# Schematic_proiect.net
KiCad netlist of a schematic drawn in EAGLE
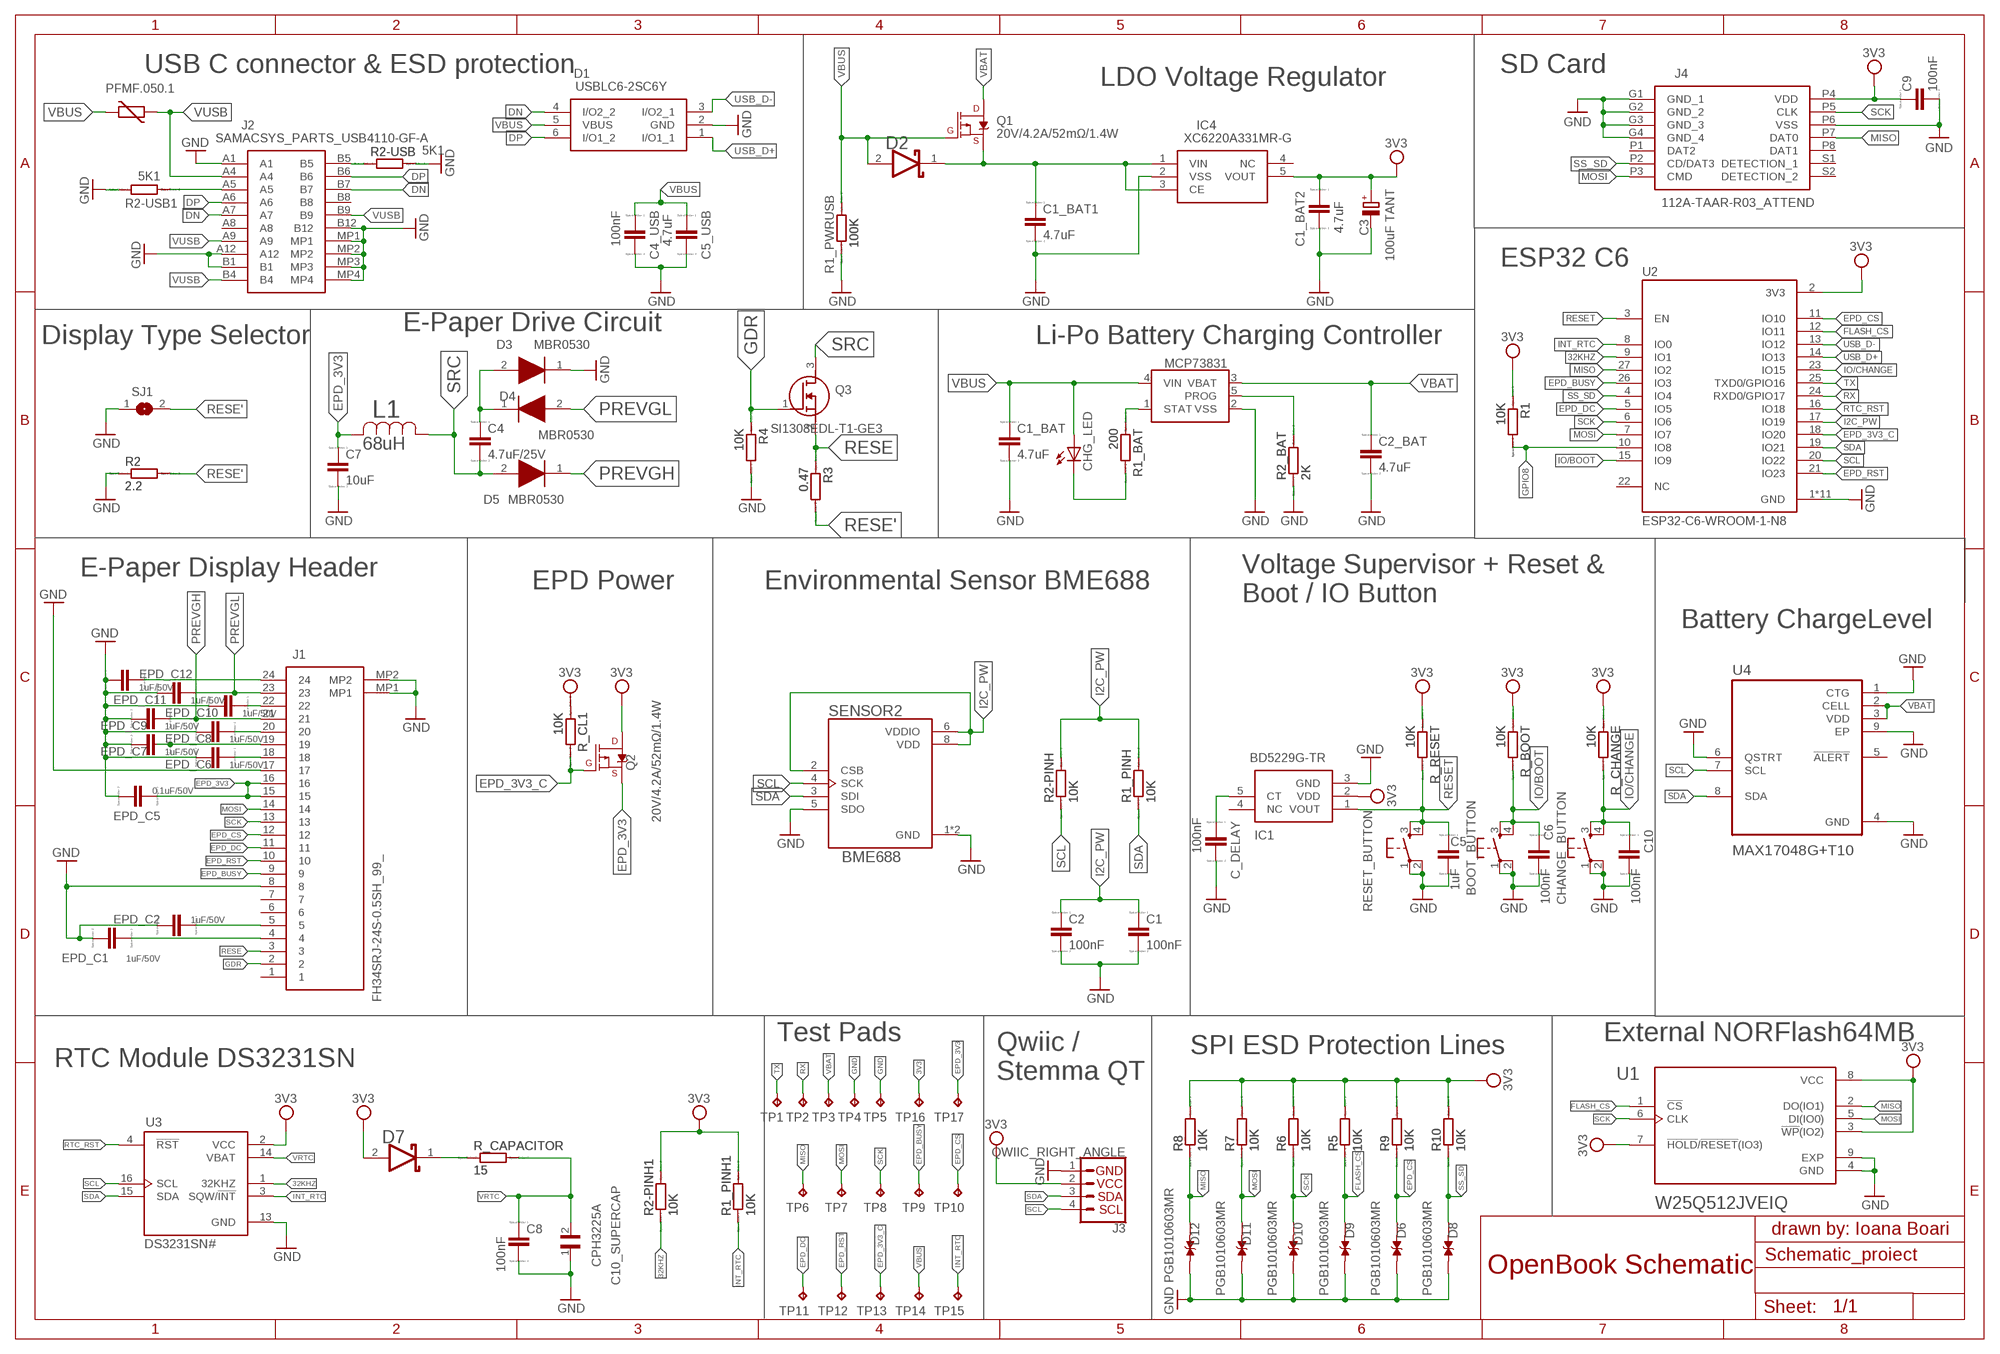
[diagram p0: schematic, sheet 1]

(export (version "E")
  (design (tool "Eeschema 10.0.6"))
  (components
    (comp (ref "BOOT_BUTTON")
      (value "BUTTON_CUSYOMV1")
      (footprint "eagle-import:MYBUTTON")
      (libsource (lib "eagle-import") (part "BUTTON_CUSYOMV1"))
    )
    (comp (ref "C1")
      (value "100nF")
      (footprint "eagle-import:ESP32_WROVER_EAGLE-LTSPICE_C0402")
      (libsource (lib "eagle-import") (part "ESP32_WROVER_EAGLE-LTSPICE_CC0402"))
    )
    (comp (ref "C1_BAT")
      (value "4.7uF")
      (footprint "eagle-import:ESP32_WROVER_EAGLE-LTSPICE_C0402")
      (libsource (lib "eagle-import") (part "ESP32_WROVER_EAGLE-LTSPICE_CC0402"))
    )
    (comp (ref "C1_BAT1")
      (value "4.7uF")
      (footprint "eagle-import:ESP32_WROVER_EAGLE-LTSPICE_C0402")
      (libsource (lib "eagle-import") (part "ESP32_WROVER_EAGLE-LTSPICE_CC0402"))
    )
    (comp (ref "C1_BAT2")
      (value "4.7uF")
      (footprint "eagle-import:EAGLE-LTSPICE_C0402")
      (libsource (lib "eagle-import") (part "EAGLE-LTSPICE_CC0402"))
    )
    (comp (ref "C2")
      (value "100nF")
      (footprint "eagle-import:ESP32_WROVER_EAGLE-LTSPICE_C0402")
      (libsource (lib "eagle-import") (part "ESP32_WROVER_EAGLE-LTSPICE_CC0402"))
    )
    (comp (ref "C2_BAT")
      (value "4.7uF")
      (footprint "eagle-import:ESP32_WROVER_EAGLE-LTSPICE_C0402")
      (libsource (lib "eagle-import") (part "ESP32_WROVER_EAGLE-LTSPICE_CC0402"))
    )
    (comp (ref "C3")
      (value "100uF TANT")
      (footprint "eagle-import:RCL_CT3528")
      (libsource (lib "eagle-import") (part "RCL_CPOL-EUCT3528"))
    )
    (comp (ref "C4")
      (value "4.7uF/25V")
      (footprint "eagle-import:ESP32_WROVER_EAGLE-LTSPICE_C0402")
      (libsource (lib "eagle-import") (part "ESP32_WROVER_EAGLE-LTSPICE_CC0402"))
    )
    (comp (ref "C4_USB")
      (value "100nF")
      (footprint "eagle-import:ESP32_WROVER_EAGLE-LTSPICE_C0402")
      (libsource (lib "eagle-import") (part "ESP32_WROVER_EAGLE-LTSPICE_CC0402"))
    )
    (comp (ref "C5")
      (value "1uF")
      (footprint "eagle-import:ESP32_WROVER_EAGLE-LTSPICE_C0402")
      (libsource (lib "eagle-import") (part "ESP32_WROVER_EAGLE-LTSPICE_CC0402"))
    )
    (comp (ref "C5_USB")
      (value "4.7uF")
      (footprint "eagle-import:ESP32_WROVER_EAGLE-LTSPICE_C0402")
      (libsource (lib "eagle-import") (part "ESP32_WROVER_EAGLE-LTSPICE_CC0402"))
    )
    (comp (ref "C6")
      (value "100nF")
      (footprint "eagle-import:ESP32_WROVER_EAGLE-LTSPICE_C0402")
      (libsource (lib "eagle-import") (part "ESP32_WROVER_EAGLE-LTSPICE_CC0402"))
    )
    (comp (ref "C7")
      (value "10uF")
      (footprint "eagle-import:ESP32_WROVER_EAGLE-LTSPICE_C0402")
      (libsource (lib "eagle-import") (part "ESP32_WROVER_EAGLE-LTSPICE_CC0402"))
    )
    (comp (ref "C8")
      (value "100nF")
      (footprint "eagle-import:ESP32_WROVER_EAGLE-LTSPICE_C0402")
      (libsource (lib "eagle-import") (part "ESP32_WROVER_EAGLE-LTSPICE_CC0402"))
    )
    (comp (ref "C9")
      (value "100nF")
      (footprint "eagle-import:ESP32_WROVER_EAGLE-LTSPICE_C0402")
      (libsource (lib "eagle-import") (part "ESP32_WROVER_EAGLE-LTSPICE_CC0402"))
    )
    (comp (ref "C10")
      (value "100nF")
      (footprint "eagle-import:ESP32_WROVER_EAGLE-LTSPICE_C0402")
      (libsource (lib "eagle-import") (part "ESP32_WROVER_EAGLE-LTSPICE_CC0402"))
    )
    (comp (ref "C10_SUPERCAP")
      (value "CPH3225A")
      (footprint "eagle-import:CAPCP3225X100N")
      (fields (field (name "MF") "Seiko Instruments"))
      (libsource (lib "eagle-import") (part "CPH3225A"))
    )
    (comp (ref "CHANGE_BUTTON")
      (value "BUTTON_CUSYOMV1")
      (footprint "eagle-import:MYBUTTON")
      (libsource (lib "eagle-import") (part "BUTTON_CUSYOMV1"))
    )
    (comp (ref "CHG_LED")
      (value "ADAFRUIT_LEDCHIP-LED0603")
      (footprint "eagle-import:ADAFRUIT_CHIP-LED0603")
      (libsource (lib "eagle-import") (part "ADAFRUIT_LEDCHIP-LED0603"))
    )
    (comp (ref "C_DELAY")
      (value "100nF")
      (footprint "eagle-import:ESP32_WROVER_EAGLE-LTSPICE_C0402")
      (libsource (lib "eagle-import") (part "ESP32_WROVER_EAGLE-LTSPICE_CC0402"))
    )
    (comp (ref "D1")
      (value "USBLC6-2SC6Y")
      (footprint "eagle-import:SOT95P280X145-6N")
      (fields (field (name "MF") "STMicroelectronics"))
      (libsource (lib "eagle-import") (part "USBLC6-2SC6Y"))
    )
    (comp (ref "D2")
      (value "ESP32_WROVER_AVX---SD0805S020S1R0_AVX_SD0805S020S1R0_0_0AVX_SD0805S020S1R0_0_0")
      (footprint "eagle-import:ESP32_WROVER_AVX---SD0805S020S1R0_AVX_SD0805S020S1R0_0")
      (fields
        (field (name "DIGIKEY_PART_NUMBER") "478-7800-1-ND")
        (field (name "MF") "AVX")
        (field (name "MOUSER_PART_NUMBER") "581-SD0805S020S1R0")
      )
      (libsource (lib "eagle-import") (part "ESP32_WROVER_AVX---SD0805S020S1R0_AVX_SD0805S020S1R0_0_0AVX_SD0805S020S1R0_0_0"))
    )
    (comp (ref "D3")
      (value "MBR0530")
      (footprint "eagle-import:SOD3716X135N")
      (fields (field (name "MF") "ON Semiconductor"))
      (libsource (lib "eagle-import") (part "MBR0530"))
    )
    (comp (ref "D4")
      (value "MBR0530")
      (footprint "eagle-import:SOD3716X135N")
      (fields (field (name "MF") "ON Semiconductor"))
      (libsource (lib "eagle-import") (part "MBR0530"))
    )
    (comp (ref "D5")
      (value "MBR0530")
      (footprint "eagle-import:SOD3716X135N")
      (fields (field (name "MF") "ON Semiconductor"))
      (libsource (lib "eagle-import") (part "MBR0530"))
    )
    (comp (ref "D6")
      (value "PGB1010603MR")
      (footprint "eagle-import:DIOC1608X36N")
      (fields (field (name "MF") "Littelfuse Inc."))
      (libsource (lib "eagle-import") (part "PGB1010603MR"))
    )
    (comp (ref "D7")
      (value "ESP32_WROVER_AVX---SD0805S020S1R0_AVX_SD0805S020S1R0_0_0AVX_SD0805S020S1R0_0_0")
      (footprint "eagle-import:ESP32_WROVER_AVX---SD0805S020S1R0_AVX_SD0805S020S1R0_0")
      (fields
        (field (name "DIGIKEY_PART_NUMBER") "478-7800-1-ND")
        (field (name "MF") "AVX")
        (field (name "MOUSER_PART_NUMBER") "581-SD0805S020S1R0")
      )
      (libsource (lib "eagle-import") (part "ESP32_WROVER_AVX---SD0805S020S1R0_AVX_SD0805S020S1R0_0_0AVX_SD0805S020S1R0_0_0"))
    )
    (comp (ref "D8")
      (value "PGB1010603MR")
      (footprint "eagle-import:DIOC1608X36N")
      (fields (field (name "MF") "Littelfuse Inc."))
      (libsource (lib "eagle-import") (part "PGB1010603MR"))
    )
    (comp (ref "D9")
      (value "PGB1010603MR")
      (footprint "eagle-import:DIOC1608X36N")
      (fields (field (name "MF") "Littelfuse Inc."))
      (libsource (lib "eagle-import") (part "PGB1010603MR"))
    )
    (comp (ref "D10")
      (value "PGB1010603MR")
      (footprint "eagle-import:DIOC1608X36N")
      (fields (field (name "MF") "Littelfuse Inc."))
      (libsource (lib "eagle-import") (part "PGB1010603MR"))
    )
    (comp (ref "D11")
      (value "PGB1010603MR")
      (footprint "eagle-import:DIOC1608X36N")
      (fields (field (name "MF") "Littelfuse Inc."))
      (libsource (lib "eagle-import") (part "PGB1010603MR"))
    )
    (comp (ref "D12")
      (value "PGB1010603MR")
      (footprint "eagle-import:DIOC1608X36N")
      (fields (field (name "MF") "Littelfuse Inc."))
      (libsource (lib "eagle-import") (part "PGB1010603MR"))
    )
    (comp (ref "EPD_C1")
      (value "1uF/50V")
      (footprint "eagle-import:ESP32_WROVER_EAGLE-LTSPICE_C0402")
      (libsource (lib "eagle-import") (part "ESP32_WROVER_EAGLE-LTSPICE_CC0402"))
    )
    (comp (ref "EPD_C2")
      (value "1uF/50V")
      (footprint "eagle-import:ESP32_WROVER_EAGLE-LTSPICE_C0402")
      (libsource (lib "eagle-import") (part "ESP32_WROVER_EAGLE-LTSPICE_CC0402"))
    )
    (comp (ref "EPD_C5")
      (value "0.1uF/50V")
      (footprint "eagle-import:ESP32_WROVER_EAGLE-LTSPICE_C0402")
      (libsource (lib "eagle-import") (part "ESP32_WROVER_EAGLE-LTSPICE_CC0402"))
    )
    (comp (ref "EPD_C6")
      (value "1uF/50V")
      (footprint "eagle-import:ESP32_WROVER_EAGLE-LTSPICE_C0402")
      (libsource (lib "eagle-import") (part "ESP32_WROVER_EAGLE-LTSPICE_CC0402"))
    )
    (comp (ref "EPD_C7")
      (value "1uF/50V")
      (footprint "eagle-import:ESP32_WROVER_EAGLE-LTSPICE_C0402")
      (libsource (lib "eagle-import") (part "ESP32_WROVER_EAGLE-LTSPICE_CC0402"))
    )
    (comp (ref "EPD_C8")
      (value "1uF/50V")
      (footprint "eagle-import:ESP32_WROVER_EAGLE-LTSPICE_C0402")
      (libsource (lib "eagle-import") (part "ESP32_WROVER_EAGLE-LTSPICE_CC0402"))
    )
    (comp (ref "EPD_C9")
      (value "1uF/50V")
      (footprint "eagle-import:ESP32_WROVER_EAGLE-LTSPICE_C0402")
      (libsource (lib "eagle-import") (part "ESP32_WROVER_EAGLE-LTSPICE_CC0402"))
    )
    (comp (ref "EPD_C10")
      (value "1uF/50V")
      (footprint "eagle-import:ESP32_WROVER_EAGLE-LTSPICE_C0402")
      (libsource (lib "eagle-import") (part "ESP32_WROVER_EAGLE-LTSPICE_CC0402"))
    )
    (comp (ref "EPD_C11")
      (value "1uF/50V")
      (footprint "eagle-import:ESP32_WROVER_EAGLE-LTSPICE_C0402")
      (libsource (lib "eagle-import") (part "ESP32_WROVER_EAGLE-LTSPICE_CC0402"))
    )
    (comp (ref "EPD_C12")
      (value "1uF/50V")
      (footprint "eagle-import:ESP32_WROVER_EAGLE-LTSPICE_C0402")
      (libsource (lib "eagle-import") (part "ESP32_WROVER_EAGLE-LTSPICE_CC0402"))
    )
    (comp (ref "IC1")
      (value "BD5229G-TR")
      (footprint "eagle-import:SOT95P280X125-5N")
      (fields (field (name "MOUSER_PART_NUMBER") "755-BD5229G-TR"))
      (libsource (lib "eagle-import") (part "BD5229G-TR"))
    )
    (comp (ref "IC4")
      (value "XC6220A331MR-G")
      (footprint "eagle-import:SOT95P280X120-5N")
      (fields (field (name "MOUSER_PART_NUMBER") "865-XC6220A331MR-G"))
      (libsource (lib "eagle-import") (part "XC6220A331MR-G"))
    )
    (comp (ref "J1")
      (value "FH34SRJ-24S-0.5SH_99_")
      (footprint "eagle-import:FH34SRJ24S05SH99")
      (fields
        (field (name "MANUFACTURER_PART_NUMBER") "FH34SRJ-24S-0.5SH(99)")
        (field (name "MOUSER_PART_NUMBER") "798-FH34SRJ24S05SH99")
      )
      (libsource (lib "eagle-import") (part "FH34SRJ-24S-0.5SH_99_"))
    )
    (comp (ref "J2")
      (value "SAMACSYS_PARTS_USB4110-GF-A")
      (footprint "eagle-import:SAMACSYS_PARTS_USB4110GFA")
      (fields
        (field (name "MANUFACTURER_PART_NUMBER") "USB4110-GF-A")
        (field (name "MOUSER_PART_NUMBER") "640-USB4110-GF-A")
      )
      (libsource (lib "eagle-import") (part "SAMACSYS_PARTS_USB4110-GF-A"))
    )
    (comp (ref "J3")
      (value "QWIIC_RIGHT_ANGLE")
      (footprint "eagle-import:JST04_1MM_RA")
      (libsource (lib "eagle-import") (part "QWIIC_CONNECTORJS-1MM"))
    )
    (comp (ref "J4")
      (value "112A-TAAR-R03_ATTEND")
      (footprint "eagle-import:112ATAARR03ATTEND")
      (fields (field (name "MANUFACTURER_PART_NUMBER") "112A-TAAR-R03 ATTEND"))
      (libsource (lib "eagle-import") (part "112A-TAAR-R03_ATTEND"))
    )
    (comp (ref "L1")
      (value "68uH")
      (footprint "eagle-import:IND_4828-WE-TPC_WRE")
      (fields
        (field (name "MANUFACTURER_PART_NUMBER") "744043680")
        (field (name "COPYRIGHT") "Copyright (C) 2024 Ultra Librarian. All rights reserved.")
      )
      (libsource (lib "eagle-import") (part "744043680IND_4828-WE-TPC_WRE"))
    )
    (comp (ref "MCP73831")
      (value "MCP73831")
      (footprint "eagle-import:ESP32_WROVER_SPARKFUN-IC-POWER_SOT23-5")
      (libsource (lib "eagle-import") (part "ESP32_WROVER_SPARKFUN-IC-POWER_MCP73831"))
    )
    (comp (ref "PFMF.050.1")
      (value "ESP32C6_VARISTORCN1812")
      (footprint "eagle-import:ESP32C6_VARISTOR_CT_CN1812")
      (libsource (lib "eagle-import") (part "ESP32C6_VARISTORCN1812"))
    )
    (comp (ref "Q1")
      (value "20V/4.2A/52mΩ/1.4W")
      (footprint "eagle-import:ESP32_WROVER_SPARKFUN-DISCRETESEMI_SOT23-3")
      (libsource (lib "eagle-import") (part "ESP32_WROVER_SPARKFUN-DISCRETESEMI_MOSFET_PCH-DMG2305UX-7"))
    )
    (comp (ref "Q2")
      (value "20V/4.2A/52mΩ/1.4W")
      (footprint "eagle-import:ESP32_WROVER_SPARKFUN-DISCRETESEMI_SOT23-3")
      (libsource (lib "eagle-import") (part "ESP32_WROVER_SPARKFUN-DISCRETESEMI_MOSFET_PCH-DMG2305UX-7"))
    )
    (comp (ref "Q3")
      (value "SI1308EDL-T1-GE3")
      (footprint "eagle-import:SOT65P210X110-3N")
      (fields (field (name "MF") "Vishay Siliconix"))
      (libsource (lib "eagle-import") (part "SI1308EDL-T1-GE3"))
    )
    (comp (ref "R1")
      (value "10K")
      (footprint "eagle-import:ESP32_WROVER_EAGLE-LTSPICE_R0402")
      (libsource (lib "eagle-import") (part "ESP32_WROVER_EAGLE-LTSPICE_RR0402"))
    )
    (comp (ref "R1_BAT")
      (value "200")
      (footprint "eagle-import:ESP32_WROVER_EAGLE-LTSPICE_R0402")
      (libsource (lib "eagle-import") (part "ESP32_WROVER_EAGLE-LTSPICE_RR0402"))
    )
    (comp (ref "R1_PINH")
      (value "10K")
      (footprint "eagle-import:ESP32_WROVER_EAGLE-LTSPICE_R0402")
      (libsource (lib "eagle-import") (part "ESP32_WROVER_EAGLE-LTSPICE_RR0402"))
    )
    (comp (ref "R1_PINH1")
      (value "10K")
      (footprint "eagle-import:ESP32_WROVER_EAGLE-LTSPICE_R0402")
      (libsource (lib "eagle-import") (part "ESP32_WROVER_EAGLE-LTSPICE_RR0402"))
    )
    (comp (ref "R1_PWRUSB")
      (value "100K")
      (footprint "eagle-import:ESP32_WROVER_EAGLE-LTSPICE_R0402")
      (libsource (lib "eagle-import") (part "ESP32_WROVER_EAGLE-LTSPICE_RR0402"))
    )
    (comp (ref "R2")
      (value "2.2")
      (footprint "eagle-import:ESP32_WROVER_EAGLE-LTSPICE_R0402")
      (libsource (lib "eagle-import") (part "ESP32_WROVER_EAGLE-LTSPICE_RR0402"))
    )
    (comp (ref "R2-PINH")
      (value "10K")
      (footprint "eagle-import:ESP32_WROVER_EAGLE-LTSPICE_R0402")
      (libsource (lib "eagle-import") (part "ESP32_WROVER_EAGLE-LTSPICE_RR0402"))
    )
    (comp (ref "R2-PINH1")
      (value "10K")
      (footprint "eagle-import:ESP32_WROVER_EAGLE-LTSPICE_R0402")
      (libsource (lib "eagle-import") (part "ESP32_WROVER_EAGLE-LTSPICE_RR0402"))
    )
    (comp (ref "R2-USB")
      (value "5K1")
      (footprint "eagle-import:ESP32_WROVER_EAGLE-LTSPICE_R0402")
      (libsource (lib "eagle-import") (part "ESP32_WROVER_EAGLE-LTSPICE_RR0402"))
    )
    (comp (ref "R2-USB1")
      (value "5K1")
      (footprint "eagle-import:ESP32_WROVER_EAGLE-LTSPICE_R0402")
      (libsource (lib "eagle-import") (part "ESP32_WROVER_EAGLE-LTSPICE_RR0402"))
    )
    (comp (ref "R2_BAT")
      (value "2K")
      (footprint "eagle-import:ESP32_WROVER_EAGLE-LTSPICE_R0402")
      (libsource (lib "eagle-import") (part "ESP32_WROVER_EAGLE-LTSPICE_RR0402"))
    )
    (comp (ref "R3")
      (value "0.47")
      (footprint "eagle-import:ESP32_WROVER_EAGLE-LTSPICE_R0402")
      (libsource (lib "eagle-import") (part "ESP32_WROVER_EAGLE-LTSPICE_RR0402"))
    )
    (comp (ref "R4")
      (value "10K")
      (footprint "eagle-import:ESP32_WROVER_EAGLE-LTSPICE_R0402")
      (libsource (lib "eagle-import") (part "ESP32_WROVER_EAGLE-LTSPICE_RR0402"))
    )
    (comp (ref "R5")
      (value "10K")
      (footprint "eagle-import:ESP32_WROVER_EAGLE-LTSPICE_R0402")
      (libsource (lib "eagle-import") (part "ESP32_WROVER_EAGLE-LTSPICE_RR0402"))
    )
    (comp (ref "R6")
      (value "10K")
      (footprint "eagle-import:ESP32_WROVER_EAGLE-LTSPICE_R0402")
      (libsource (lib "eagle-import") (part "ESP32_WROVER_EAGLE-LTSPICE_RR0402"))
    )
    (comp (ref "R7")
      (value "10K")
      (footprint "eagle-import:ESP32_WROVER_EAGLE-LTSPICE_R0402")
      (libsource (lib "eagle-import") (part "ESP32_WROVER_EAGLE-LTSPICE_RR0402"))
    )
    (comp (ref "R8")
      (value "10K")
      (footprint "eagle-import:ESP32_WROVER_EAGLE-LTSPICE_R0402")
      (libsource (lib "eagle-import") (part "ESP32_WROVER_EAGLE-LTSPICE_RR0402"))
    )
    (comp (ref "R9")
      (value "10K")
      (footprint "eagle-import:ESP32_WROVER_EAGLE-LTSPICE_R0402")
      (libsource (lib "eagle-import") (part "ESP32_WROVER_EAGLE-LTSPICE_RR0402"))
    )
    (comp (ref "R10")
      (value "10K")
      (footprint "eagle-import:ESP32_WROVER_EAGLE-LTSPICE_R0402")
      (libsource (lib "eagle-import") (part "ESP32_WROVER_EAGLE-LTSPICE_RR0402"))
    )
    (comp (ref "RESET_BUTTON")
      (value "BUTTON_CUSYOMV1")
      (footprint "eagle-import:MYBUTTON")
      (libsource (lib "eagle-import") (part "BUTTON_CUSYOMV1"))
    )
    (comp (ref "R_BOOT")
      (value "10K")
      (footprint "eagle-import:ESP32_WROVER_EAGLE-LTSPICE_R0402")
      (libsource (lib "eagle-import") (part "ESP32_WROVER_EAGLE-LTSPICE_RR0402"))
    )
    (comp (ref "R_CAPACITOR")
      (value "15")
      (footprint "eagle-import:ESP32_WROVER_EAGLE-LTSPICE_R0402")
      (libsource (lib "eagle-import") (part "ESP32_WROVER_EAGLE-LTSPICE_RR0402"))
    )
    (comp (ref "R_CHANGE")
      (value "10K")
      (footprint "eagle-import:ESP32_WROVER_EAGLE-LTSPICE_R0402")
      (libsource (lib "eagle-import") (part "ESP32_WROVER_EAGLE-LTSPICE_RR0402"))
    )
    (comp (ref "R_CL1")
      (value "10K")
      (footprint "eagle-import:ESP32_WROVER_EAGLE-LTSPICE_R0402")
      (libsource (lib "eagle-import") (part "ESP32_WROVER_EAGLE-LTSPICE_RR0402"))
    )
    (comp (ref "R_RESET")
      (value "10K")
      (footprint "eagle-import:ESP32_WROVER_EAGLE-LTSPICE_R0402")
      (libsource (lib "eagle-import") (part "ESP32_WROVER_EAGLE-LTSPICE_RR0402"))
    )
    (comp (ref "SENSOR2")
      (value "BME688")
      (footprint "eagle-import:ESP32_WROVER_BME680_PSON80P300X300X100-8N")
      (fields (field (name "MF") "Bosch Sensortec") (field (name "MP") "BME680"))
      (libsource (lib "eagle-import") (part "ESP32_WROVER_BME680_BME680"))
    )
    (comp (ref "SJ1") (value "SJ") (footprint "eagle-import:SJ") (libsource (lib "eagle-import") (part "SJ")))
    (comp (ref "TP1")
      (value "TPTP20R")
      (footprint "eagle-import:TP20R")
      (libsource (lib "eagle-import") (part "TPTP20R"))
    )
    (comp (ref "TP2")
      (value "TPTP20R")
      (footprint "eagle-import:TP20R")
      (libsource (lib "eagle-import") (part "TPTP20R"))
    )
    (comp (ref "TP3")
      (value "TPTP20R")
      (footprint "eagle-import:TP20R")
      (libsource (lib "eagle-import") (part "TPTP20R"))
    )
    (comp (ref "TP4")
      (value "TPTP20R")
      (footprint "eagle-import:TP20R")
      (libsource (lib "eagle-import") (part "TPTP20R"))
    )
    (comp (ref "TP5")
      (value "TPTP20R")
      (footprint "eagle-import:TP20R")
      (libsource (lib "eagle-import") (part "TPTP20R"))
    )
    (comp (ref "TP6")
      (value "TPTP20R")
      (footprint "eagle-import:TP20R")
      (libsource (lib "eagle-import") (part "TPTP20R"))
    )
    (comp (ref "TP7")
      (value "TPTP20R")
      (footprint "eagle-import:TP20R")
      (libsource (lib "eagle-import") (part "TPTP20R"))
    )
    (comp (ref "TP8")
      (value "TPTP20R")
      (footprint "eagle-import:TP20R")
      (libsource (lib "eagle-import") (part "TPTP20R"))
    )
    (comp (ref "TP9")
      (value "TPTP20R")
      (footprint "eagle-import:TP20R")
      (libsource (lib "eagle-import") (part "TPTP20R"))
    )
    (comp (ref "TP10")
      (value "TPTP20R")
      (footprint "eagle-import:TP20R")
      (libsource (lib "eagle-import") (part "TPTP20R"))
    )
    (comp (ref "TP11")
      (value "TPTP20R")
      (footprint "eagle-import:TP20R")
      (libsource (lib "eagle-import") (part "TPTP20R"))
    )
    (comp (ref "TP12")
      (value "TPTP20R")
      (footprint "eagle-import:TP20R")
      (libsource (lib "eagle-import") (part "TPTP20R"))
    )
    (comp (ref "TP13")
      (value "TPTP20R")
      (footprint "eagle-import:TP20R")
      (libsource (lib "eagle-import") (part "TPTP20R"))
    )
    (comp (ref "TP14")
      (value "TPTP20R")
      (footprint "eagle-import:TP20R")
      (libsource (lib "eagle-import") (part "TPTP20R"))
    )
    (comp (ref "TP15")
      (value "TPTP20R")
      (footprint "eagle-import:TP20R")
      (libsource (lib "eagle-import") (part "TPTP20R"))
    )
    (comp (ref "TP16")
      (value "TPTP20R")
      (footprint "eagle-import:TP20R")
      (libsource (lib "eagle-import") (part "TPTP20R"))
    )
    (comp (ref "TP17")
      (value "TPTP20R")
      (footprint "eagle-import:TP20R")
      (libsource (lib "eagle-import") (part "TPTP20R"))
    )
    (comp (ref "U1")
      (value "W25Q512JVEIQ")
      (footprint "eagle-import:SON127P600X800X80-9N")
      (fields (field (name "MF") "Winbond Electronics"))
      (libsource (lib "eagle-import") (part "W25Q512JVEIQ"))
    )
    (comp (ref "U2")
      (value "ESP32-C6-WROOM-1-N8")
      (footprint "eagle-import:XCVR_ESP32-C6-WROOM-1-N8")
      (fields (field (name "MF") "Espressif Systems"))
      (libsource (lib "eagle-import") (part "ESP32-C6-WROOM-1-N8"))
    )
    (comp (ref "U3")
      (value "DS3231SN#")
      (footprint "eagle-import:SOIC127P1032X265-16N")
      (fields (field (name "MF") "Analog Devices"))
      (libsource (lib "eagle-import") (part "DS3231SN#"))
    )
    (comp (ref "U4")
      (value "MAX17048G+T10")
      (footprint "eagle-import:SON50P200X200X80-9N")
      (fields (field (name "MF") "Analog Devices"))
      (libsource (lib "eagle-import") (part "MAX17048G+T10"))
    )
  )
  (nets
    (net (code "1") (name "3V3") (class "Default")
      (node (ref "C1_BAT2") (pin "1") (pinfunction "1_1") (pintype "passive"))
      (node (ref "C3") (pin "+") (pinfunction "+_+") (pintype "passive"))
      (node (ref "C9") (pin "1") (pinfunction "1_1") (pintype "passive"))
      (node (ref "D7") (pin "2") (pinfunction "ANODE_2") (pintype "bidirectional"))
      (node (ref "IC1") (pin "2") (pinfunction "VDD_2") (pintype "bidirectional"))
      (node (ref "IC4") (pin "5") (pinfunction "VOUT_5") (pintype "bidirectional"))
      (node (ref "J3") (pin "2") (pinfunction "2_2") (pintype "power_in"))
      (node (ref "J4") (pin "P4") (pinfunction "VDD_P4") (pintype "bidirectional"))
      (node (ref "Q2") (pin "3") (pinfunction "D_3") (pintype "bidirectional"))
      (node (ref "R1") (pin "1") (pinfunction "1_1") (pintype "passive"))
      (node (ref "R10") (pin "2") (pinfunction "2_2") (pintype "passive"))
      (node (ref "R1_PINH1") (pin "2") (pinfunction "2_2") (pintype "passive"))
      (node (ref "R2-PINH1") (pin "2") (pinfunction "2_2") (pintype "passive"))
      (node (ref "R5") (pin "2") (pinfunction "2_2") (pintype "passive"))
      (node (ref "R6") (pin "2") (pinfunction "2_2") (pintype "passive"))
      (node (ref "R7") (pin "2") (pinfunction "2_2") (pintype "passive"))
      (node (ref "R8") (pin "2") (pinfunction "2_2") (pintype "passive"))
      (node (ref "R9") (pin "2") (pinfunction "2_2") (pintype "passive"))
      (node (ref "R_BOOT") (pin "1") (pinfunction "1_1") (pintype "passive"))
      (node (ref "R_CHANGE") (pin "1") (pinfunction "1_1") (pintype "passive"))
      (node (ref "R_CL1") (pin "1") (pinfunction "1_1") (pintype "passive"))
      (node (ref "R_RESET") (pin "1") (pinfunction "1_1") (pintype "passive"))
      (node (ref "TP16") (pin "TP") (pinfunction "TP_TP") (pintype "input"))
      (node (ref "U1") (pin "3") (pinfunction "~{WP}(IO2)_3") (pintype "bidirectional"))
      (node (ref "U1") (pin "7") (pinfunction "~{HOLD}/~{RESET}(IO3)_7") (pintype "bidirectional"))
      (node (ref "U1") (pin "8") (pinfunction "VCC_8") (pintype "power_in"))
      (node (ref "U2") (pin "2") (pinfunction "3V3_2") (pintype "power_in"))
      (node (ref "U3") (pin "2") (pinfunction "VCC_2") (pintype "power_in"))
    )
    (net (code "2") (name "32KHZ") (class "Default")
      (node (ref "R2-PINH1") (pin "1") (pinfunction "1_1") (pintype "passive"))
      (node (ref "U2") (pin "9") (pinfunction "IO1_9") (pintype "bidirectional"))
      (node (ref "U3") (pin "1") (pinfunction "32KHZ_1") (pintype "output"))
    )
    (net (code "3") (name "DN") (class "Default")
      (node (ref "D1") (pin "4") (pinfunction "I/O2_2_4") (pintype "bidirectional"))
      (node (ref "J2") (pin "A7") (pinfunction "A7_A7") (pintype "bidirectional"))
      (node (ref "J2") (pin "B7") (pinfunction "B7_B7") (pintype "bidirectional"))
    )
    (net (code "4") (name "DP") (class "Default")
      (node (ref "D1") (pin "6") (pinfunction "I/O1_2_6") (pintype "bidirectional"))
      (node (ref "J2") (pin "A6") (pinfunction "A6_A6") (pintype "bidirectional"))
      (node (ref "J2") (pin "B6") (pinfunction "B6_B6") (pintype "bidirectional"))
    )
    (net (code "5") (name "EPD_3V3") (class "Default")
      (node (ref "C7") (pin "1") (pinfunction "1_1") (pintype "passive"))
      (node (ref "EPD_C5") (pin "1") (pinfunction "1_1") (pintype "passive"))
      (node (ref "J1") (pin "15") (pinfunction "15_15") (pintype "bidirectional"))
      (node (ref "J1") (pin "16") (pinfunction "16_16") (pintype "bidirectional"))
      (node (ref "L1") (pin "2") (pinfunction "2_2") (pintype "passive"))
      (node (ref "Q2") (pin "2") (pinfunction "S_2") (pintype "bidirectional"))
      (node (ref "TP17") (pin "TP") (pinfunction "TP_TP") (pintype "input"))
    )
    (net (code "6") (name "EPD_3V3_C") (class "Default")
      (node (ref "Q2") (pin "1") (pinfunction "G_1") (pintype "bidirectional"))
      (node (ref "R_CL1") (pin "2") (pinfunction "2_2") (pintype "passive"))
      (node (ref "TP13") (pin "TP") (pinfunction "TP_TP") (pintype "input"))
      (node (ref "U2") (pin "18") (pinfunction "IO20_18") (pintype "bidirectional"))
    )
    (net (code "7") (name "EPD_BUSY") (class "Default")
      (node (ref "J1") (pin "9") (pinfunction "9_9") (pintype "bidirectional"))
      (node (ref "TP9") (pin "TP") (pinfunction "TP_TP") (pintype "input"))
      (node (ref "U2") (pin "26") (pinfunction "IO3_26") (pintype "bidirectional"))
    )
    (net (code "8") (name "EPD_CS") (class "Default")
      (node (ref "D6") (pin "1") (pinfunction "1_1") (pintype "passive"))
      (node (ref "J1") (pin "12") (pinfunction "12_12") (pintype "bidirectional"))
      (node (ref "R9") (pin "1") (pinfunction "1_1") (pintype "passive"))
      (node (ref "TP10") (pin "TP") (pinfunction "TP_TP") (pintype "input"))
      (node (ref "U2") (pin "11") (pinfunction "IO10_11") (pintype "bidirectional"))
    )
    (net (code "9") (name "EPD_DC") (class "Default")
      (node (ref "J1") (pin "11") (pinfunction "11_11") (pintype "bidirectional"))
      (node (ref "TP11") (pin "TP") (pinfunction "TP_TP") (pintype "input"))
      (node (ref "U2") (pin "5") (pinfunction "IO5_5") (pintype "bidirectional"))
    )
    (net (code "10") (name "EPD_RST") (class "Default")
      (node (ref "J1") (pin "10") (pinfunction "10_10") (pintype "bidirectional"))
      (node (ref "TP12") (pin "TP") (pinfunction "TP_TP") (pintype "input"))
      (node (ref "U2") (pin "21") (pinfunction "IO23_21") (pintype "bidirectional"))
    )
    (net (code "11") (name "FLASH_CS") (class "Default")
      (node (ref "D9") (pin "1") (pinfunction "1_1") (pintype "passive"))
      (node (ref "R5") (pin "1") (pinfunction "1_1") (pintype "passive"))
      (node (ref "U1") (pin "1") (pinfunction "~{CS}_1") (pintype "input"))
      (node (ref "U2") (pin "12") (pinfunction "IO11_12") (pintype "bidirectional"))
    )
    (net (code "12") (name "GDR") (class "Default")
      (node (ref "J1") (pin "2") (pinfunction "2_2") (pintype "bidirectional"))
      (node (ref "Q3") (pin "1") (pinfunction "G_1") (pintype "bidirectional"))
      (node (ref "R4") (pin "1") (pinfunction "1_1") (pintype "passive"))
    )
    (net (code "13") (name "GND") (class "Default")
      (node (ref "BOOT_BUTTON") (pin "1") (pinfunction "1_1") (pintype "passive"))
      (node (ref "BOOT_BUTTON") (pin "2") (pinfunction "2_2") (pintype "passive"))
      (node (ref "C1") (pin "2") (pinfunction "2_2") (pintype "passive"))
      (node (ref "C10") (pin "2") (pinfunction "2_2") (pintype "passive"))
      (node (ref "C10_SUPERCAP") (pin "1") (pinfunction "1_1") (pintype "passive"))
      (node (ref "C1_BAT") (pin "2") (pinfunction "2_2") (pintype "passive"))
      (node (ref "C1_BAT1") (pin "2") (pinfunction "2_2") (pintype "passive"))
      (node (ref "C1_BAT2") (pin "2") (pinfunction "2_2") (pintype "passive"))
      (node (ref "C2") (pin "2") (pinfunction "2_2") (pintype "passive"))
      (node (ref "C2_BAT") (pin "2") (pinfunction "2_2") (pintype "passive"))
      (node (ref "C3") (pin "-") (pinfunction "-_-") (pintype "passive"))
      (node (ref "C4_USB") (pin "2") (pinfunction "2_2") (pintype "passive"))
      (node (ref "C5") (pin "2") (pinfunction "2_2") (pintype "passive"))
      (node (ref "C5_USB") (pin "2") (pinfunction "2_2") (pintype "passive"))
      (node (ref "C6") (pin "2") (pinfunction "2_2") (pintype "passive"))
      (node (ref "C7") (pin "2") (pinfunction "2_2") (pintype "passive"))
      (node (ref "C8") (pin "2") (pinfunction "2_2") (pintype "passive"))
      (node (ref "C9") (pin "2") (pinfunction "2_2") (pintype "passive"))
      (node (ref "CHANGE_BUTTON") (pin "1") (pinfunction "1_1") (pintype "passive"))
      (node (ref "CHANGE_BUTTON") (pin "2") (pinfunction "2_2") (pintype "passive"))
      (node (ref "C_DELAY") (pin "2") (pinfunction "2_2") (pintype "passive"))
      (node (ref "D1") (pin "2") (pinfunction "GND_2") (pintype "bidirectional"))
      (node (ref "D10") (pin "2") (pinfunction "2_2") (pintype "passive"))
      (node (ref "D11") (pin "2") (pinfunction "2_2") (pintype "passive"))
      (node (ref "D12") (pin "2") (pinfunction "2_2") (pintype "passive"))
      (node (ref "D3") (pin "1") (pinfunction "K_1") (pintype "bidirectional"))
      (node (ref "D6") (pin "2") (pinfunction "2_2") (pintype "passive"))
      (node (ref "D8") (pin "2") (pinfunction "2_2") (pintype "passive"))
      (node (ref "D9") (pin "2") (pinfunction "2_2") (pintype "passive"))
      (node (ref "EPD_C1") (pin "2") (pinfunction "2_2") (pintype "passive"))
      (node (ref "EPD_C10") (pin "2") (pinfunction "2_2") (pintype "passive"))
      (node (ref "EPD_C11") (pin "2") (pinfunction "2_2") (pintype "passive"))
      (node (ref "EPD_C12") (pin "2") (pinfunction "2_2") (pintype "passive"))
      (node (ref "EPD_C2") (pin "2") (pinfunction "2_2") (pintype "passive"))
      (node (ref "EPD_C5") (pin "2") (pinfunction "2_2") (pintype "passive"))
      (node (ref "EPD_C6") (pin "2") (pinfunction "2_2") (pintype "passive"))
      (node (ref "EPD_C7") (pin "2") (pinfunction "2_2") (pintype "passive"))
      (node (ref "EPD_C8") (pin "2") (pinfunction "2_2") (pintype "passive"))
      (node (ref "EPD_C9") (pin "2") (pinfunction "2_2") (pintype "passive"))
      (node (ref "IC1") (pin "3") (pinfunction "GND_3") (pintype "bidirectional"))
      (node (ref "IC4") (pin "2") (pinfunction "VSS_2") (pintype "bidirectional"))
      (node (ref "J1") (pin "17") (pinfunction "17_17") (pintype "bidirectional"))
      (node (ref "J1") (pin "8") (pinfunction "8_8") (pintype "bidirectional"))
      (node (ref "J1") (pin "MP1") (pinfunction "MP1_MP1") (pintype "bidirectional"))
      (node (ref "J1") (pin "MP2") (pinfunction "MP2_MP2") (pintype "bidirectional"))
      (node (ref "J2") (pin "A1") (pinfunction "A1_A1") (pintype "bidirectional"))
      (node (ref "J2") (pin "A12") (pinfunction "A12_A12") (pintype "bidirectional"))
      (node (ref "J2") (pin "B1") (pinfunction "B1_B1") (pintype "bidirectional"))
      (node (ref "J2") (pin "B12") (pinfunction "B12_B12") (pintype "bidirectional"))
      (node (ref "J2") (pin "MP1") (pinfunction "MP1_MP1") (pintype "bidirectional"))
      (node (ref "J2") (pin "MP2") (pinfunction "MP2_MP2") (pintype "bidirectional"))
      (node (ref "J2") (pin "MP3") (pinfunction "MP3_MP3") (pintype "bidirectional"))
      (node (ref "J2") (pin "MP4") (pinfunction "MP4_MP4") (pintype "bidirectional"))
      (node (ref "J3") (pin "1") (pinfunction "1_1") (pintype "power_in"))
      (node (ref "J4") (pin "G1") (pinfunction "GND_1_G1") (pintype "bidirectional"))
      (node (ref "J4") (pin "G2") (pinfunction "GND_2_G2") (pintype "bidirectional"))
      (node (ref "J4") (pin "G3") (pinfunction "GND_3_G3") (pintype "bidirectional"))
      (node (ref "J4") (pin "G4") (pinfunction "GND_4_G4") (pintype "bidirectional"))
      (node (ref "J4") (pin "P6") (pinfunction "VSS_P6") (pintype "bidirectional"))
      (node (ref "MCP73831") (pin "2") (pinfunction "VSS_2") (pintype "power_in"))
      (node (ref "R1_PWRUSB") (pin "1") (pinfunction "1_1") (pintype "passive"))
      (node (ref "R2") (pin "1") (pinfunction "1_1") (pintype "passive"))
      (node (ref "R2-USB") (pin "2") (pinfunction "2_2") (pintype "passive"))
      (node (ref "R2-USB1") (pin "1") (pinfunction "1_1") (pintype "passive"))
      (node (ref "R2_BAT") (pin "1") (pinfunction "1_1") (pintype "passive"))
      (node (ref "R4") (pin "2") (pinfunction "2_2") (pintype "passive"))
      (node (ref "RESET_BUTTON") (pin "1") (pinfunction "1_1") (pintype "passive"))
      (node (ref "RESET_BUTTON") (pin "2") (pinfunction "2_2") (pintype "passive"))
      (node (ref "SENSOR2") (pin "1") (pinfunction "GND_1") (pintype "power_in"))
      (node (ref "SENSOR2") (pin "5") (pinfunction "SDO_5") (pintype "bidirectional"))
      (node (ref "SENSOR2") (pin "7") (pinfunction "GND_7") (pintype "power_in"))
      (node (ref "SJ1") (pin "1") (pinfunction "1_1") (pintype "passive"))
      (node (ref "TP4") (pin "TP") (pinfunction "TP_TP") (pintype "input"))
      (node (ref "TP5") (pin "TP") (pinfunction "TP_TP") (pintype "input"))
      (node (ref "U1") (pin "4") (pinfunction "GND_4") (pintype "power_in"))
      (node (ref "U1") (pin "9") (pinfunction "EXP_9") (pintype "passive"))
      (node (ref "U2") (pin "1") (pinfunction "GND_1") (pintype "power_in"))
      (node (ref "U2") (pin "28") (pinfunction "GND_28") (pintype "power_in"))
      (node (ref "U2") (pin "29_1") (pinfunction "GND_29_1") (pintype "power_in"))
      (node (ref "U2") (pin "29_2") (pinfunction "GND_29_2") (pintype "power_in"))
      (node (ref "U2") (pin "29_3") (pinfunction "GND_29_3") (pintype "power_in"))
      (node (ref "U2") (pin "29_4") (pinfunction "GND_29_4") (pintype "power_in"))
      (node (ref "U2") (pin "29_5") (pinfunction "GND_29_5") (pintype "power_in"))
      (node (ref "U2") (pin "29_6") (pinfunction "GND_29_6") (pintype "power_in"))
      (node (ref "U2") (pin "29_7") (pinfunction "GND_29_7") (pintype "power_in"))
      (node (ref "U2") (pin "29_8") (pinfunction "GND_29_8") (pintype "power_in"))
      (node (ref "U2") (pin "29_9") (pinfunction "GND_29_9") (pintype "power_in"))
      (node (ref "U3") (pin "13") (pinfunction "GND_13") (pintype "power_in"))
      (node (ref "U4") (pin "1") (pinfunction "CTG_1") (pintype "power_in"))
      (node (ref "U4") (pin "4") (pinfunction "GND_4") (pintype "power_in"))
      (node (ref "U4") (pin "6") (pinfunction "QSTRT_6") (pintype "input"))
      (node (ref "U4") (pin "9") (pinfunction "EP_9") (pintype "power_in"))
    )
    (net (code "14") (name "GPIO8") (class "Default")
      (node (ref "R1") (pin "2") (pinfunction "2_2") (pintype "passive"))
      (node (ref "U2") (pin "10") (pinfunction "IO8_10") (pintype "bidirectional"))
    )
    (net (code "15") (name "I2C_PW") (class "Default")
      (node (ref "C1") (pin "1") (pinfunction "1_1") (pintype "passive"))
      (node (ref "C2") (pin "1") (pinfunction "1_1") (pintype "passive"))
      (node (ref "R1_PINH") (pin "2") (pinfunction "2_2") (pintype "passive"))
      (node (ref "R2-PINH") (pin "2") (pinfunction "2_2") (pintype "passive"))
      (node (ref "SENSOR2") (pin "2") (pinfunction "CSB_2") (pintype "input"))
      (node (ref "SENSOR2") (pin "6") (pinfunction "VDDIO_6") (pintype "power_in"))
      (node (ref "SENSOR2") (pin "8") (pinfunction "VDD_8") (pintype "power_in"))
      (node (ref "U2") (pin "17") (pinfunction "IO19_17") (pintype "bidirectional"))
    )
    (net (code "16") (name "INT_RTC") (class "Default")
      (node (ref "R1_PINH1") (pin "1") (pinfunction "1_1") (pintype "passive"))
      (node (ref "TP15") (pin "TP") (pinfunction "TP_TP") (pintype "input"))
      (node (ref "U2") (pin "8") (pinfunction "IO0_8") (pintype "bidirectional"))
      (node (ref "U3") (pin "3") (pinfunction "SQW/~{INT}_3") (pintype "output"))
    )
    (net (code "17") (name "IO{slash}BOOT") (class "Default")
      (node (ref "BOOT_BUTTON") (pin "3") (pinfunction "3_3") (pintype "passive"))
      (node (ref "BOOT_BUTTON") (pin "4") (pinfunction "4_4") (pintype "passive"))
      (node (ref "C6") (pin "1") (pinfunction "1_1") (pintype "passive"))
      (node (ref "R_BOOT") (pin "2") (pinfunction "2_2") (pintype "passive"))
      (node (ref "U2") (pin "15") (pinfunction "IO9_15") (pintype "bidirectional"))
    )
    (net (code "18") (name "IO{slash}CHANGE") (class "Default")
      (node (ref "C10") (pin "1") (pinfunction "1_1") (pintype "passive"))
      (node (ref "CHANGE_BUTTON") (pin "3") (pinfunction "3_3") (pintype "passive"))
      (node (ref "CHANGE_BUTTON") (pin "4") (pinfunction "4_4") (pintype "passive"))
      (node (ref "R_CHANGE") (pin "2") (pinfunction "2_2") (pintype "passive"))
      (node (ref "U2") (pin "23") (pinfunction "IO15_23") (pintype "bidirectional"))
    )
    (net (code "19") (name "MISO") (class "Default")
      (node (ref "D12") (pin "1") (pinfunction "1_1") (pintype "passive"))
      (node (ref "J4") (pin "P7") (pinfunction "DAT0_P7") (pintype "bidirectional"))
      (node (ref "R8") (pin "1") (pinfunction "1_1") (pintype "passive"))
      (node (ref "TP6") (pin "TP") (pinfunction "TP_TP") (pintype "input"))
      (node (ref "U1") (pin "2") (pinfunction "DO(IO1)_2") (pintype "bidirectional"))
      (node (ref "U2") (pin "27") (pinfunction "IO2_27") (pintype "bidirectional"))
    )
    (net (code "20") (name "MOSI") (class "Default")
      (node (ref "D11") (pin "1") (pinfunction "1_1") (pintype "passive"))
      (node (ref "J1") (pin "14") (pinfunction "14_14") (pintype "bidirectional"))
      (node (ref "J4") (pin "P3") (pinfunction "CMD_P3") (pintype "bidirectional"))
      (node (ref "R7") (pin "1") (pinfunction "1_1") (pintype "passive"))
      (node (ref "TP7") (pin "TP") (pinfunction "TP_TP") (pintype "input"))
      (node (ref "U1") (pin "5") (pinfunction "DI(IO0)_5") (pintype "bidirectional"))
      (node (ref "U2") (pin "7") (pinfunction "IO7_7") (pintype "bidirectional"))
    )
    (net (code "21") (name "Net-(CHG_LED-PadC)") (class "Default")
      (node (ref "CHG_LED") (pin "C") (pinfunction "C_C") (pintype "passive"))
      (node (ref "R1_BAT") (pin "2") (pinfunction "2_2") (pintype "passive"))
    )
    (net (code "22") (name "Net-(D2-CATHODE)") (class "Default")
      (node (ref "C1_BAT1") (pin "1") (pinfunction "1_1") (pintype "passive"))
      (node (ref "D2") (pin "1") (pinfunction "CATHODE_1") (pintype "bidirectional"))
      (node (ref "IC4") (pin "1") (pinfunction "VIN_1") (pintype "bidirectional"))
      (node (ref "IC4") (pin "3") (pinfunction "CE_3") (pintype "bidirectional"))
      (node (ref "Q1") (pin "2") (pinfunction "S_2") (pintype "bidirectional"))
    )
    (net (code "23") (name "Net-(D3-A)") (class "Default")
      (node (ref "C4") (pin "1") (pinfunction "1_1") (pintype "passive"))
      (node (ref "D3") (pin "2") (pinfunction "A_2") (pintype "bidirectional"))
      (node (ref "D4") (pin "1") (pinfunction "K_1") (pintype "bidirectional"))
    )
    (net (code "24") (name "Net-(D7-CATHODE)") (class "Default")
      (node (ref "D7") (pin "1") (pinfunction "CATHODE_1") (pintype "bidirectional"))
      (node (ref "R_CAPACITOR") (pin "1") (pinfunction "1_1") (pintype "passive"))
    )
    (net (code "25") (name "Net-(EPD_C1-Pad1)") (class "Default")
      (node (ref "EPD_C1") (pin "1") (pinfunction "1_1") (pintype "passive"))
      (node (ref "J1") (pin "4") (pinfunction "4_4") (pintype "bidirectional"))
    )
    (net (code "26") (name "Net-(EPD_C2-Pad1)") (class "Default")
      (node (ref "EPD_C2") (pin "1") (pinfunction "1_1") (pintype "passive"))
      (node (ref "J1") (pin "5") (pinfunction "5_5") (pintype "bidirectional"))
    )
    (net (code "27") (name "Net-(EPD_C6-Pad1)") (class "Default")
      (node (ref "EPD_C6") (pin "1") (pinfunction "1_1") (pintype "passive"))
      (node (ref "J1") (pin "18") (pinfunction "18_18") (pintype "bidirectional"))
    )
    (net (code "28") (name "Net-(EPD_C7-Pad1)") (class "Default")
      (node (ref "EPD_C7") (pin "1") (pinfunction "1_1") (pintype "passive"))
      (node (ref "J1") (pin "19") (pinfunction "19_19") (pintype "bidirectional"))
    )
    (net (code "29") (name "Net-(EPD_C8-Pad1)") (class "Default")
      (node (ref "EPD_C8") (pin "1") (pinfunction "1_1") (pintype "passive"))
      (node (ref "J1") (pin "20") (pinfunction "20_20") (pintype "bidirectional"))
    )
    (net (code "30") (name "Net-(EPD_C10-Pad1)") (class "Default")
      (node (ref "EPD_C10") (pin "1") (pinfunction "1_1") (pintype "passive"))
      (node (ref "J1") (pin "22") (pinfunction "22_22") (pintype "bidirectional"))
    )
    (net (code "31") (name "Net-(EPD_C12-Pad1)") (class "Default")
      (node (ref "EPD_C12") (pin "1") (pinfunction "1_1") (pintype "passive"))
      (node (ref "J1") (pin "24") (pinfunction "24_24") (pintype "bidirectional"))
    )
    (net (code "32") (name "Net-(IC1-CT)") (class "Default")
      (node (ref "C_DELAY") (pin "1") (pinfunction "1_1") (pintype "passive"))
      (node (ref "IC1") (pin "5") (pinfunction "CT_5") (pintype "bidirectional"))
    )
    (net (code "33") (name "Net-(J2-PadA5)") (class "Default")
      (node (ref "J2") (pin "A5") (pinfunction "A5_A5") (pintype "bidirectional"))
      (node (ref "R2-USB1") (pin "2") (pinfunction "2_2") (pintype "passive"))
    )
    (net (code "34") (name "Net-(J2-PadB5)") (class "Default")
      (node (ref "J2") (pin "B5") (pinfunction "B5_B5") (pintype "bidirectional"))
      (node (ref "R2-USB") (pin "1") (pinfunction "1_1") (pintype "passive"))
    )
    (net (code "35") (name "Net-(MCP73831-PROG)") (class "Default")
      (node (ref "MCP73831") (pin "5") (pinfunction "PROG_5") (pintype "input"))
      (node (ref "R2_BAT") (pin "2") (pinfunction "2_2") (pintype "passive"))
    )
    (net (code "36") (name "Net-(MCP73831-STAT)") (class "Default")
      (node (ref "MCP73831") (pin "1") (pinfunction "STAT_1") (pintype "output"))
      (node (ref "R1_BAT") (pin "1") (pinfunction "1_1") (pintype "passive"))
    )
    (net (code "37") (name "PREVGH") (class "Default")
      (node (ref "D5") (pin "1") (pinfunction "K_1") (pintype "bidirectional"))
      (node (ref "EPD_C9") (pin "1") (pinfunction "1_1") (pintype "passive"))
      (node (ref "J1") (pin "21") (pinfunction "21_21") (pintype "bidirectional"))
    )
    (net (code "38") (name "PREVGL") (class "Default")
      (node (ref "D4") (pin "2") (pinfunction "A_2") (pintype "bidirectional"))
      (node (ref "EPD_C11") (pin "1") (pinfunction "1_1") (pintype "passive"))
      (node (ref "J1") (pin "23") (pinfunction "23_23") (pintype "bidirectional"))
    )
    (net (code "39") (name "RESE") (class "Default")
      (node (ref "J1") (pin "3") (pinfunction "3_3") (pintype "bidirectional"))
      (node (ref "Q3") (pin "2") (pinfunction "S_2") (pintype "bidirectional"))
      (node (ref "R3") (pin "1") (pinfunction "1_1") (pintype "passive"))
    )
    (net (code "40") (name "RESE'") (class "Default")
      (node (ref "R2") (pin "2") (pinfunction "2_2") (pintype "passive"))
      (node (ref "R3") (pin "2") (pinfunction "2_2") (pintype "passive"))
      (node (ref "SJ1") (pin "2") (pinfunction "2_2") (pintype "passive"))
    )
    (net (code "41") (name "RESET") (class "Default")
      (node (ref "C5") (pin "1") (pinfunction "1_1") (pintype "passive"))
      (node (ref "IC1") (pin "1") (pinfunction "VOUT_1") (pintype "bidirectional"))
      (node (ref "RESET_BUTTON") (pin "3") (pinfunction "3_3") (pintype "passive"))
      (node (ref "RESET_BUTTON") (pin "4") (pinfunction "4_4") (pintype "passive"))
      (node (ref "R_RESET") (pin "2") (pinfunction "2_2") (pintype "passive"))
      (node (ref "U2") (pin "3") (pinfunction "EN_3") (pintype "input"))
    )
    (net (code "42") (name "RTC_RST") (class "Default")
      (node (ref "U2") (pin "16") (pinfunction "IO18_16") (pintype "bidirectional"))
      (node (ref "U3") (pin "4") (pinfunction "~{RST}_4") (pintype "input"))
    )
    (net (code "43") (name "RX") (class "Default")
      (node (ref "TP2") (pin "TP") (pinfunction "TP_TP") (pintype "input"))
      (node (ref "U2") (pin "24") (pinfunction "RXD0/GPIO17_24") (pintype "bidirectional"))
    )
    (net (code "44") (name "SCK") (class "Default")
      (node (ref "D10") (pin "1") (pinfunction "1_1") (pintype "passive"))
      (node (ref "J1") (pin "13") (pinfunction "13_13") (pintype "bidirectional"))
      (node (ref "J4") (pin "P5") (pinfunction "CLK_P5") (pintype "bidirectional"))
      (node (ref "R6") (pin "1") (pinfunction "1_1") (pintype "passive"))
      (node (ref "TP8") (pin "TP") (pinfunction "TP_TP") (pintype "input"))
      (node (ref "U1") (pin "6") (pinfunction "CLK_6") (pintype "input"))
      (node (ref "U2") (pin "6") (pinfunction "IO6_6") (pintype "bidirectional"))
    )
    (net (code "45") (name "SCL") (class "Default")
      (node (ref "J3") (pin "4") (pinfunction "4_4") (pintype "passive"))
      (node (ref "R2-PINH") (pin "1") (pinfunction "1_1") (pintype "passive"))
      (node (ref "SENSOR2") (pin "4") (pinfunction "SCK_4") (pintype "input"))
      (node (ref "U2") (pin "20") (pinfunction "IO22_20") (pintype "bidirectional"))
      (node (ref "U3") (pin "16") (pinfunction "SCL_16") (pintype "input"))
      (node (ref "U4") (pin "7") (pinfunction "SCL_7") (pintype "input"))
    )
    (net (code "46") (name "SDA") (class "Default")
      (node (ref "J3") (pin "3") (pinfunction "3_3") (pintype "passive"))
      (node (ref "R1_PINH") (pin "1") (pinfunction "1_1") (pintype "passive"))
      (node (ref "SENSOR2") (pin "3") (pinfunction "SDI_3") (pintype "bidirectional"))
      (node (ref "U2") (pin "19") (pinfunction "IO21_19") (pintype "bidirectional"))
      (node (ref "U3") (pin "15") (pinfunction "SDA_15") (pintype "bidirectional"))
      (node (ref "U4") (pin "8") (pinfunction "SDA_8") (pintype "bidirectional"))
    )
    (net (code "47") (name "SRC") (class "Default")
      (node (ref "C4") (pin "2") (pinfunction "2_2") (pintype "passive"))
      (node (ref "D5") (pin "2") (pinfunction "A_2") (pintype "bidirectional"))
      (node (ref "L1") (pin "1") (pinfunction "1_1") (pintype "passive"))
      (node (ref "Q3") (pin "3") (pinfunction "D_3") (pintype "bidirectional"))
    )
    (net (code "48") (name "SS_SD") (class "Default")
      (node (ref "D8") (pin "1") (pinfunction "1_1") (pintype "passive"))
      (node (ref "J4") (pin "P2") (pinfunction "CD/DAT3_P2") (pintype "bidirectional"))
      (node (ref "R10") (pin "1") (pinfunction "1_1") (pintype "passive"))
      (node (ref "U2") (pin "4") (pinfunction "IO4_4") (pintype "bidirectional"))
    )
    (net (code "49") (name "TX") (class "Default")
      (node (ref "TP1") (pin "TP") (pinfunction "TP_TP") (pintype "input"))
      (node (ref "U2") (pin "25") (pinfunction "TXD0/GPIO16_25") (pintype "bidirectional"))
    )
    (net (code "50") (name "USB_D+") (class "Default")
      (node (ref "D1") (pin "1") (pinfunction "I/O1_1_1") (pintype "bidirectional"))
      (node (ref "U2") (pin "14") (pinfunction "IO13_14") (pintype "bidirectional"))
    )
    (net (code "51") (name "USB_D-") (class "Default")
      (node (ref "D1") (pin "3") (pinfunction "I/O2_1_3") (pintype "bidirectional"))
      (node (ref "U2") (pin "13") (pinfunction "IO12_13") (pintype "bidirectional"))
    )
    (net (code "52") (name "VBAT") (class "Default")
      (node (ref "C2_BAT") (pin "1") (pinfunction "1_1") (pintype "passive"))
      (node (ref "MCP73831") (pin "3") (pinfunction "VBAT_3") (pintype "power_in"))
      (node (ref "Q1") (pin "3") (pinfunction "D_3") (pintype "bidirectional"))
      (node (ref "TP3") (pin "TP") (pinfunction "TP_TP") (pintype "input"))
      (node (ref "U4") (pin "2") (pinfunction "CELL_2") (pintype "power_in"))
      (node (ref "U4") (pin "3") (pinfunction "VDD_3") (pintype "power_in"))
    )
    (net (code "53") (name "VBUS") (class "Default")
      (node (ref "C1_BAT") (pin "1") (pinfunction "1_1") (pintype "passive"))
      (node (ref "C4_USB") (pin "1") (pinfunction "1_1") (pintype "passive"))
      (node (ref "C5_USB") (pin "1") (pinfunction "1_1") (pintype "passive"))
      (node (ref "CHG_LED") (pin "A") (pinfunction "A_A") (pintype "passive"))
      (node (ref "D1") (pin "5") (pinfunction "VBUS_5") (pintype "bidirectional"))
      (node (ref "D2") (pin "2") (pinfunction "ANODE_2") (pintype "bidirectional"))
      (node (ref "MCP73831") (pin "4") (pinfunction "VIN_4") (pintype "power_in"))
      (node (ref "PFMF.050.1") (pin "2") (pinfunction "2_2") (pintype "passive"))
      (node (ref "Q1") (pin "1") (pinfunction "G_1") (pintype "bidirectional"))
      (node (ref "R1_PWRUSB") (pin "2") (pinfunction "2_2") (pintype "passive"))
      (node (ref "TP14") (pin "TP") (pinfunction "TP_TP") (pintype "input"))
    )
    (net (code "54") (name "VRTC") (class "Default")
      (node (ref "C10_SUPERCAP") (pin "2") (pinfunction "2_2") (pintype "passive"))
      (node (ref "C8") (pin "1") (pinfunction "1_1") (pintype "passive"))
      (node (ref "R_CAPACITOR") (pin "2") (pinfunction "2_2") (pintype "passive"))
      (node (ref "U3") (pin "14") (pinfunction "VBAT_14") (pintype "power_in"))
    )
    (net (code "55") (name "VUSB") (class "Default")
      (node (ref "J2") (pin "A4") (pinfunction "A4_A4") (pintype "bidirectional"))
      (node (ref "J2") (pin "A9") (pinfunction "A9_A9") (pintype "bidirectional"))
      (node (ref "J2") (pin "B4") (pinfunction "B4_B4") (pintype "bidirectional"))
      (node (ref "J2") (pin "B9") (pinfunction "B9_B9") (pintype "bidirectional"))
      (node (ref "PFMF.050.1") (pin "1") (pinfunction "1_1") (pintype "passive"))
    )
    (net (code "56") (name "unconnected-(IC1-NC-Pad4)") (class "Default")
      (node (ref "IC1") (pin "4") (pinfunction "NC_4") (pintype "no_connect"))
    )
    (net (code "57") (name "unconnected-(IC4-NC-Pad4)") (class "Default")
      (node (ref "IC4") (pin "4") (pinfunction "NC_4") (pintype "no_connect"))
    )
    (net (code "58") (name "unconnected-(J1-Pad1)") (class "Default")
      (node (ref "J1") (pin "1") (pinfunction "1_1") (pintype "bidirectional"))
    )
    (net (code "59") (name "unconnected-(J1-Pad6)") (class "Default")
      (node (ref "J1") (pin "6") (pinfunction "6_6") (pintype "bidirectional"))
    )
    (net (code "60") (name "unconnected-(J1-Pad7)") (class "Default")
      (node (ref "J1") (pin "7") (pinfunction "7_7") (pintype "bidirectional"))
    )
    (net (code "61") (name "unconnected-(J2-PadA8)") (class "Default")
      (node (ref "J2") (pin "A8") (pinfunction "A8_A8") (pintype "bidirectional"))
    )
    (net (code "62") (name "unconnected-(J2-PadB8)") (class "Default")
      (node (ref "J2") (pin "B8") (pinfunction "B8_B8") (pintype "bidirectional"))
    )
    (net (code "63") (name "unconnected-(J4-DAT1-PadP8)") (class "Default")
      (node (ref "J4") (pin "P8") (pinfunction "DAT1_P8") (pintype "bidirectional"))
    )
    (net (code "64") (name "unconnected-(J4-DAT2-PadP1)") (class "Default")
      (node (ref "J4") (pin "P1") (pinfunction "DAT2_P1") (pintype "bidirectional"))
    )
    (net (code "65") (name "unconnected-(J4-DETECTION_1-PadS1)") (class "Default")
      (node (ref "J4") (pin "S1") (pinfunction "DETECTION_1_S1") (pintype "bidirectional"))
    )
    (net (code "66") (name "unconnected-(J4-DETECTION_2-PadS2)") (class "Default")
      (node (ref "J4") (pin "S2") (pinfunction "DETECTION_2_S2") (pintype "bidirectional"))
    )
    (net (code "67") (name "unconnected-(U2-NC-Pad22)") (class "Default")
      (node (ref "U2") (pin "22") (pinfunction "NC_22") (pintype "no_connect"))
    )
    (net (code "68") (name "unconnected-(U4-~{ALERT}-Pad5)") (class "Default")
      (node (ref "U4") (pin "5") (pinfunction "~{ALERT}_5") (pintype "output"))
    )
  )
)
